# design.net
KiCad netlist of a schematic drawn in Altium Designer
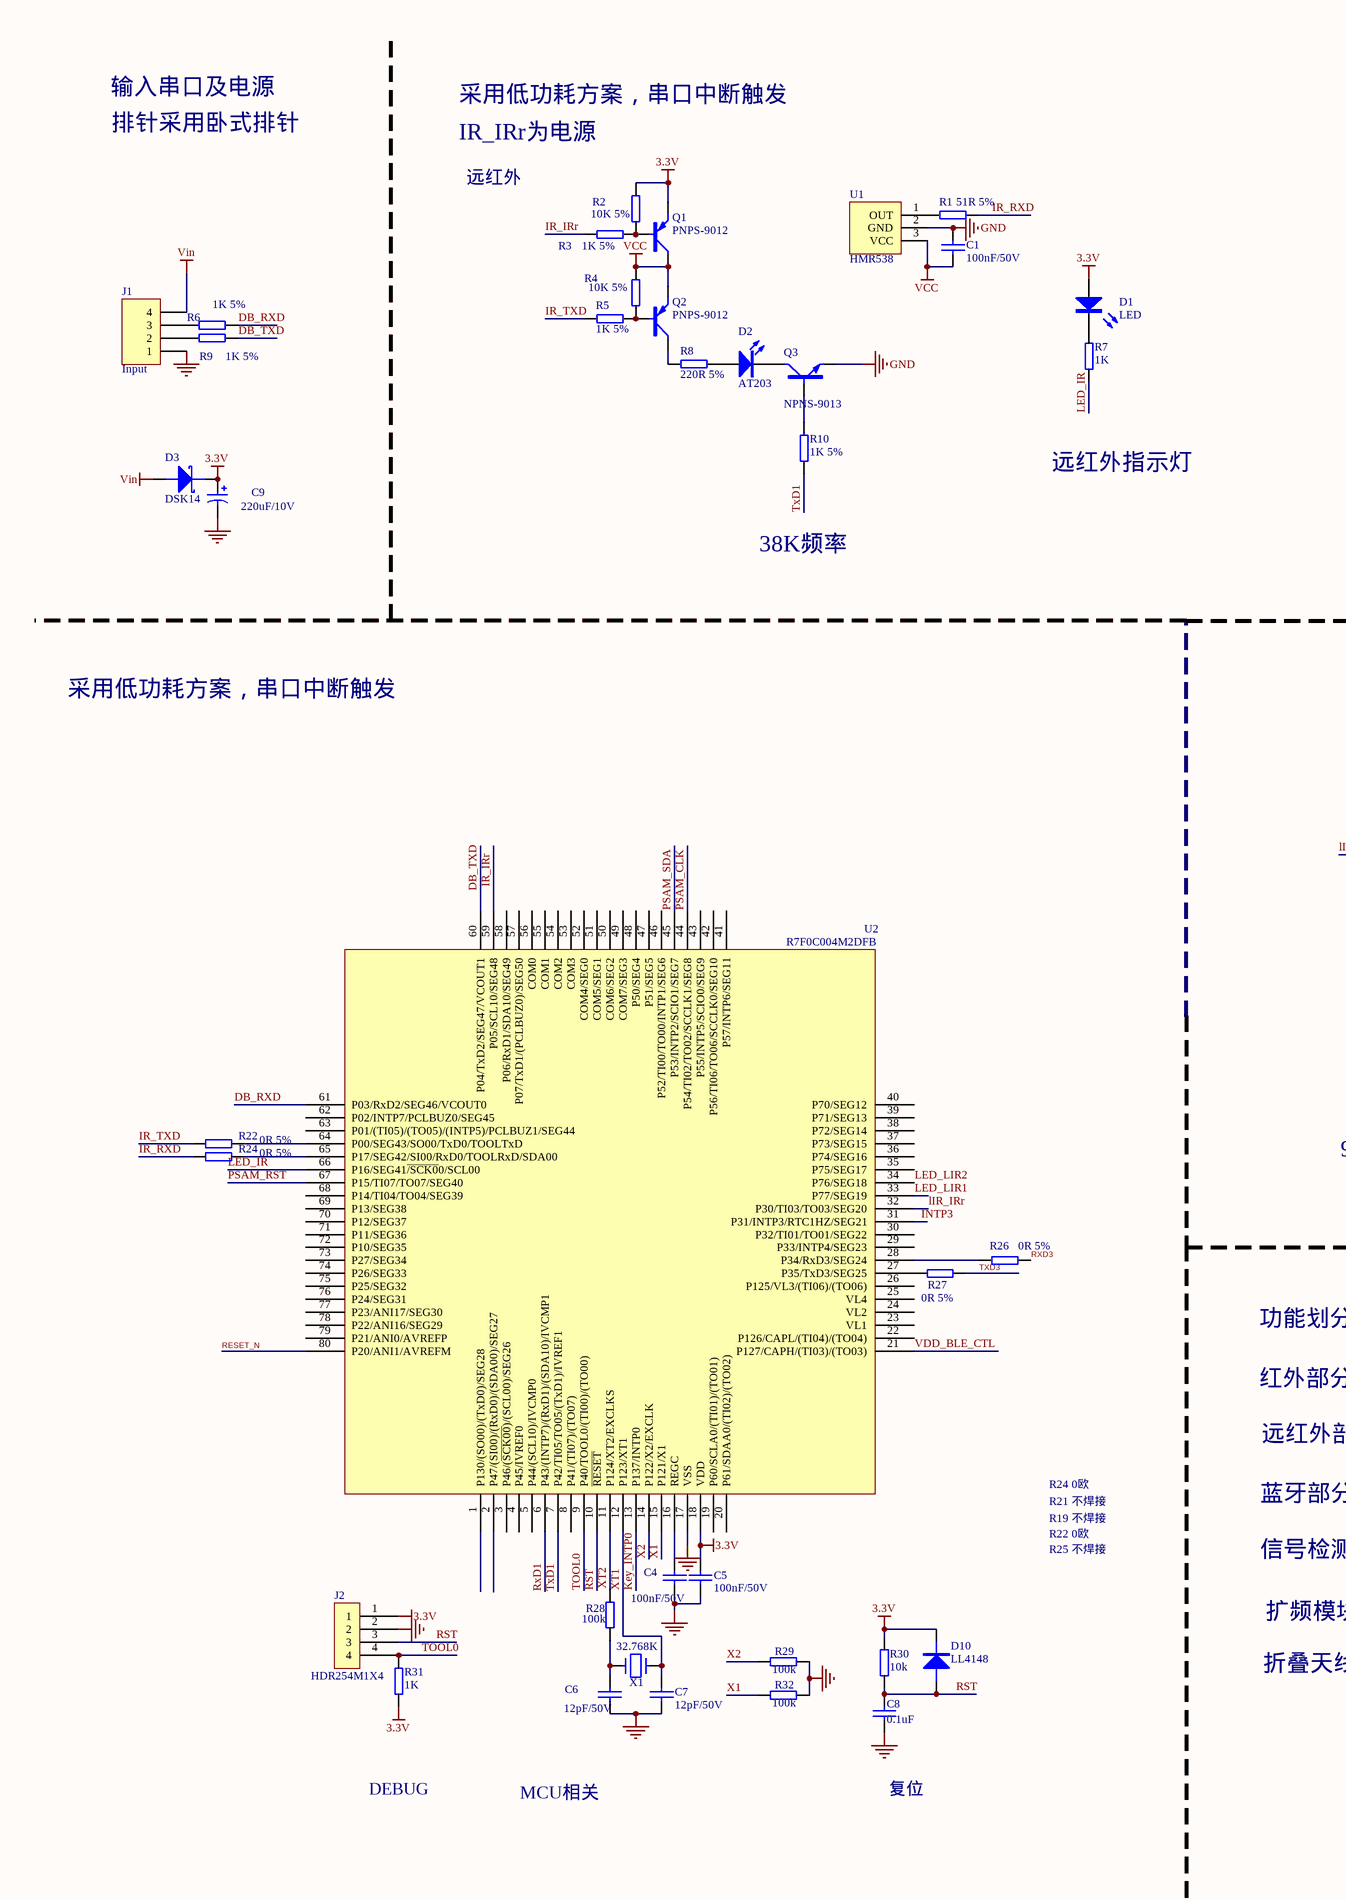
[diagram p0: 多合一红外工具.SchDoc, left]
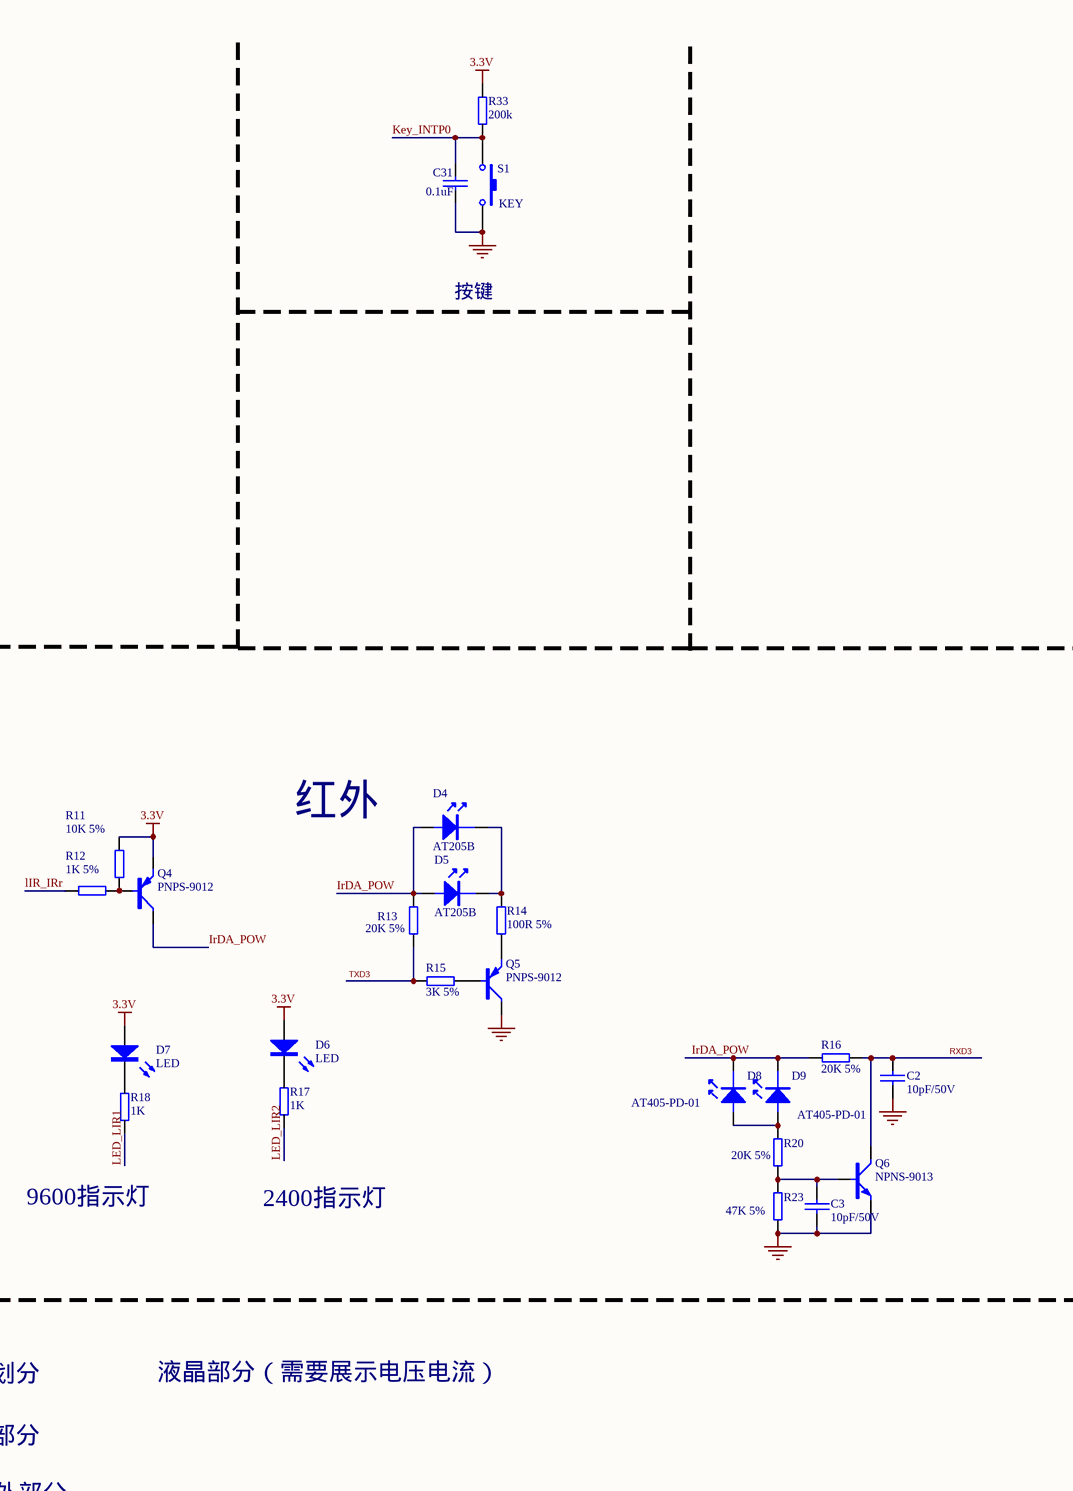
[diagram p1: 多合一红外工具.SchDoc, right]

(export (version "E")
  (design (tool "Eeschema 10.0.6"))
  (components
    (comp (ref "C1")
      (value "100nF/50V")
      (footprint "CAP0603")
      (description "104pF,50 V,±10%,0603,国巨,CC0603KRX7R9BB104")
      (fields (field (name "PART NUMBER") "101020103-0021"))
      (libsource (lib "Database_Libs2") (part "CC03K7R9_100N"))
    )
    (comp (ref "C2")
      (value "10pF/50V")
      (footprint "CAP0603")
      (description "10pF,50 V,±5%,0603,X7R,国巨,CC0603JRNPO9BN100")
      (fields (field (name "PART NUMBER") "101020103-0014"))
      (libsource (lib "Database_Libs2") (part "CC03JPO9_10P"))
    )
    (comp (ref "C3")
      (value "10pF/50V")
      (footprint "CAP0603")
      (description "10pF,50 V,±5%,0603,X7R,国巨,CC0603JRNPO9BN100")
      (fields (field (name "PART NUMBER") "101020103-0014"))
      (libsource (lib "Database_Libs2") (part "CC03JPO9_10P"))
    )
    (comp (ref "C4")
      (value "100nF/50V")
      (footprint "CAP0603")
      (description "104pF,50 V,±10%,0603,国巨,CC0603KRX7R9BB104")
      (fields (field (name "PART NUMBER") "101020103-0021"))
      (libsource (lib "Database_Libs2") (part "CC03K7R9_100N"))
    )
    (comp (ref "C5")
      (value "100nF/50V")
      (footprint "CAP0603")
      (description "104pF,50 V,±10%,0603,国巨,CC0603KRX7R9BB104")
      (fields (field (name "PART NUMBER") "101020103-0021"))
      (libsource (lib "Database_Libs2") (part "CC03K7R9_100N"))
    )
    (comp (ref "C6")
      (value "12pF/50V")
      (footprint "CAP0603")
      (description "12P,50 V,±5%,0603,国巨,CC0603JRNPO9BN12")
      (fields (field (name "PART NUMBER") "101020103-0005"))
      (libsource (lib "Database_Libs2") (part "CC03JPO9_12P"))
    )
    (comp (ref "C7")
      (value "12pF/50V")
      (footprint "CAP0603")
      (description "12P,50 V,±5%,0603,国巨,CC0603JRNPO9BN12")
      (fields (field (name "PART NUMBER") "101020103-0005"))
      (libsource (lib "Database_Libs2") (part "CC03JPO9_12P"))
    )
    (comp (ref "C8")
      (value "0.1uF")
      (footprint "C0603")
      (description "无极性电容")
      (libsource (lib "CBB_Lib_SCH") (part "CAP"))
    )
    (comp (ref "C9")
      (value "220uF/10V")
      (footprint "CAT7343")
      (description "220uF,10 V,±10%,7343,AVX/ KEMET,T491D227K010AT")
      (fields (field (name "PART NUMBER") "1010205-0001"))
      (libsource (lib "Database_Libs2") (part "CT6MATAJ_220U"))
    )
    (comp (ref "C31")
      (value "0.1uF")
      (footprint "C0603")
      (description "无极性电容")
      (libsource (lib "CBB_Lib_SCH") (part "CAP"))
    )
    (comp (ref "D1")
      (value "LED")
      (footprint "LED2_300")
      (description "圆形插件,3mm 圆形,插件,红光,湖北匡通电子有限公司,3BB4HC")
      (fields (field (name "PART NUMBER") "101040102-0001"))
      (libsource (lib "Database_Libs2") (part "01-LED_T3R"))
    )
    (comp (ref "D2")
      (value "AT203")
      (footprint "IR_254_532_300")
      (description "DIP-2,φ3,插件,红光,上海品观电子有限公司/可得,AT203")
      (fields (field (name "PART NUMBER") "101040102-0010"))
      (libsource (lib "Database_Libs2") (part "01_AT203"))
    )
    (comp (ref "D3")
      (value "DSK14")
      (footprint "SOD-123FL")
      (description "DSK14,SOD-123FL,1 A,40 V,28 V,台湾强茂集团苏州群鑫电子,DSK14")
      (fields (field (name "PART NUMBER") "101040101-0043"))
      (libsource (lib "Database_Libs2") (part "02_DSK14"))
    )
    (comp (ref "D4")
      (value "AT205B")
      (footprint "IR_254_1000_500")
      (description "直插,Φ5.8mm圆头透明色，,0.1 A,4 V,5 V,上海品观电子有限公司,AT205B")
      (fields (field (name "PART NUMBER") "101040101-0034"))
      (libsource (lib "Database_Libs2") (part "01_AT205B"))
    )
    (comp (ref "D5")
      (value "AT205B")
      (footprint "IR_254_1000_500")
      (description "直插,Φ5.8mm圆头透明色，,0.1 A,4 V,5 V,上海品观电子有限公司,AT205B")
      (fields (field (name "PART NUMBER") "101040101-0034"))
      (libsource (lib "Database_Libs2") (part "01_AT205B"))
    )
    (comp (ref "D6")
      (value "LED")
      (footprint "LED2_300")
      (description "圆形插件,3mm 圆形,插件,红光,湖北匡通电子有限公司,3BB4HC")
      (fields (field (name "PART NUMBER") "101040102-0001"))
      (libsource (lib "Database_Libs2") (part "01-LED_T3R"))
    )
    (comp (ref "D7")
      (value "LED")
      (footprint "LED2_300")
      (description "圆形插件,3mm 圆形,插件,红光,湖北匡通电子有限公司,3BB4HC")
      (fields (field (name "PART NUMBER") "101040102-0001"))
      (libsource (lib "Database_Libs2") (part "01-LED_T3R"))
    )
    (comp (ref "D8")
      (value "AT405-PD-01")
      (footprint "IR_254_1000_500")
      (description "Φ5.8mm圆头黑色，光电接收管,Φ5.8mm,0.01 A,1.2 V,60 V,上海品观电子,AT405-PD-01")
      (fields (field (name "PART NUMBER") "101040101-0035"))
      (libsource (lib "Database_Libs2") (part "01_AT405-PD-01"))
    )
    (comp (ref "D9")
      (value "AT405-PD-01")
      (footprint "IR_254_1000_500")
      (description "Φ5.8mm圆头黑色，光电接收管,Φ5.8mm,0.01 A,1.2 V,60 V,上海品观电子,AT405-PD-01")
      (fields (field (name "PART NUMBER") "101040101-0035"))
      (libsource (lib "Database_Libs2") (part "01_AT405-PD-01"))
    )
    (comp (ref "D10")
      (value "LL4148")
      (footprint "SOD-123FL")
      (description "4148,4148,0.2 A,1 V,100 V,先科,LL4148")
      (fields (field (name "PART NUMBER") "101040101-0005"))
      (libsource (lib "Database_Libs2") (part "02_LL4148"))
    )
    (comp (ref "J1")
      (value "Input")
      (footprint "HDR1X4")
      (description "Header, 4-Pin")
      (libsource (lib "CBB_Lib_SCH") (part "Header 4"))
    )
    (comp (ref "J2")
      (value "HDR254M1X4")
      (footprint "HDR1X4")
      (fields (field (name "PUBLISHER") "Altium Limited"))
      (libsource (lib "SCH_LIB_WX") (part "HDR254M1X4"))
    )
    (comp (ref "Q1")
      (value "PNPS-9012")
      (footprint "SOT-23")
      (description "9012,PNP,SOT-23,JCET;长电,S9012")
      (fields (field (name "PART NUMBER") "101040201-0001"))
      (libsource (lib "Database_Libs2") (part "03_PNPS-9012"))
    )
    (comp (ref "Q2")
      (value "PNPS-9012")
      (footprint "SOT-23")
      (description "9012,PNP,SOT-23,JCET;长电,S9012")
      (fields (field (name "PART NUMBER") "101040201-0001"))
      (libsource (lib "Database_Libs2") (part "03_PNPS-9012"))
    )
    (comp (ref "Q3")
      (value "NPNS-9013")
      (footprint "SOT-23")
      (description "9013,NPN,SOT-23,长电,S9013")
      (fields (field (name "PART NUMBER") "101040201-0002"))
      (libsource (lib "Database_Libs2") (part "03_NPNS-9013"))
    )
    (comp (ref "Q4")
      (value "PNPS-9012")
      (footprint "SOT-23")
      (description "9012,PNP,SOT-23,JCET;长电,S9012")
      (fields (field (name "PART NUMBER") "101040201-0001"))
      (libsource (lib "Database_Libs2") (part "03_PNPS-9012"))
    )
    (comp (ref "Q5")
      (value "PNPS-9012")
      (footprint "SOT-23")
      (description "9012,PNP,SOT-23,JCET;长电,S9012")
      (fields (field (name "PART NUMBER") "101040201-0001"))
      (libsource (lib "Database_Libs2") (part "03_PNPS-9012"))
    )
    (comp (ref "Q6")
      (value "NPNS-9013")
      (footprint "SOT-23")
      (description "9013,NPN,SOT-23,长电,S9013")
      (fields (field (name "PART NUMBER") "101040201-0002"))
      (libsource (lib "Database_Libs2") (part "03_NPNS-9013"))
    )
    (comp (ref "R1")
      (value "51R 5%")
      (footprint "RES0603")
      (description "国巨,±5%,0603,,155 ℃,-55 ℃,RC0603JR-0751RL,无铅,100 ppm/℃,1/10W,,51欧")
      (fields (field (name "PART NUMBER") "101010103-0037"))
      (libsource (lib "Database_Libs2") (part "RC03J_51R"))
    )
    (comp (ref "R2")
      (value "10K 5%")
      (footprint "RES0603")
      (description "国巨,±5%,0603,,155 ℃,-55 ℃,RC0603JR-0710KL,无铅,200 ppm/℃,1/10W,,10K")
      (fields (field (name "PART NUMBER") "101010103-0003"))
      (libsource (lib "Database_Libs2") (part "RC03J_10K"))
    )
    (comp (ref "R3")
      (value "1K 5%")
      (footprint "RES0603")
      (description "1K,±5%,1/10W,0603,国巨,RC0603JR-071KL")
      (fields (field (name "PART NUMBER") "101010103-0008"))
      (libsource (lib "Database_Libs2") (part "RC03J_1K"))
    )
    (comp (ref "R4")
      (value "10K 5%")
      (footprint "RES0603")
      (description "国巨,±5%,0603,,155 ℃,-55 ℃,RC0603JR-0710KL,无铅,200 ppm/℃,1/10W,,10K")
      (fields (field (name "PART NUMBER") "101010103-0003"))
      (libsource (lib "Database_Libs2") (part "RC03J_10K"))
    )
    (comp (ref "R5")
      (value "1K 5%")
      (footprint "RES0603")
      (description "1K,±5%,1/10W,0603,国巨,RC0603JR-071KL")
      (fields (field (name "PART NUMBER") "101010103-0008"))
      (libsource (lib "Database_Libs2") (part "RC03J_1K"))
    )
    (comp (ref "R6")
      (value "1K 5%")
      (footprint "RES0603")
      (description "1K,±5%,1/10W,0603,国巨,RC0603JR-071KL")
      (fields (field (name "PART NUMBER") "101010103-0008"))
      (libsource (lib "Database_Libs2") (part "RC03J_1K"))
    )
    (comp (ref "R7") (value "1K") (footprint "R0603") (libsource (lib "CBB_Lib_SCH") (part "RES")))
    (comp (ref "R8")
      (value "220R 5%")
      (footprint "RES0603")
      (description "220±5%,1/10W,0603,国巨,RC0603JR-07220RL")
      (fields (field (name "PART NUMBER") "101010103-0019"))
      (libsource (lib "Database_Libs2") (part "RC03J_220R"))
    )
    (comp (ref "R9")
      (value "1K 5%")
      (footprint "RES0603")
      (description "1K,±5%,1/10W,0603,国巨,RC0603JR-071KL")
      (fields (field (name "PART NUMBER") "101010103-0008"))
      (libsource (lib "Database_Libs2") (part "RC03J_1K"))
    )
    (comp (ref "R10")
      (value "1K 5%")
      (footprint "RES0603")
      (description "1K,±5%,1/10W,0603,国巨,RC0603JR-071KL")
      (fields (field (name "PART NUMBER") "101010103-0008"))
      (libsource (lib "Database_Libs2") (part "RC03J_1K"))
    )
    (comp (ref "R11")
      (value "10K 5%")
      (footprint "RES0603")
      (description "国巨,±5%,0603,,155 ℃,-55 ℃,RC0603JR-0710KL,无铅,200 ppm/℃,1/10W,,10K")
      (fields (field (name "PART NUMBER") "101010103-0003"))
      (libsource (lib "Database_Libs2") (part "RC03J_10K"))
    )
    (comp (ref "R12")
      (value "1K 5%")
      (footprint "RES0603")
      (description "1K,±5%,1/10W,0603,国巨,RC0603JR-071KL")
      (fields (field (name "PART NUMBER") "101010103-0008"))
      (libsource (lib "Database_Libs2") (part "RC03J_1K"))
    )
    (comp (ref "R13")
      (value "20K 5%")
      (footprint "RES0603")
      (description "国巨,±5%,0603,,155 ℃,-55 ℃,RC0603JR-0720KL,无铅,200 ppm/℃,1/10W,,20K")
      (fields (field (name "PART NUMBER") "101010103-0004"))
      (libsource (lib "Database_Libs2") (part "RC03J_20K"))
    )
    (comp (ref "R14")
      (value "100R 5%")
      (footprint "RES0603")
      (description "100R,±5%,1/10W,0603,国巨,RC0603JR-07100RL")
      (fields (field (name "PART NUMBER") "101010103-0022"))
      (libsource (lib "Database_Libs2") (part "RC03J_100R"))
    )
    (comp (ref "R15")
      (value "3K 5%")
      (footprint "RES0603")
      (description "国巨,±5%,0603,,155 ℃,-55 ℃,RC0603JR-073KL,无铅,100 ppm/℃,1/10W,,3K")
      (fields (field (name "PART NUMBER") "101010103-0006"))
      (libsource (lib "Database_Libs2") (part "RC03J_3K"))
    )
    (comp (ref "R16")
      (value "20K 5%")
      (footprint "RES0603")
      (description "国巨,±5%,0603,,155 ℃,-55 ℃,RC0603JR-0720KL,无铅,200 ppm/℃,1/10W,,20K")
      (fields (field (name "PART NUMBER") "101010103-0004"))
      (libsource (lib "Database_Libs2") (part "RC03J_20K"))
    )
    (comp (ref "R17") (value "1K") (footprint "R0603") (libsource (lib "CBB_Lib_SCH") (part "RES")))
    (comp (ref "R18") (value "1K") (footprint "R0603") (libsource (lib "CBB_Lib_SCH") (part "RES")))
    (comp (ref "R20")
      (value "20K 5%")
      (footprint "RES0603")
      (description "国巨,±5%,0603,,155 ℃,-55 ℃,RC0603JR-0720KL,无铅,200 ppm/℃,1/10W,,20K")
      (fields (field (name "PART NUMBER") "101010103-0004"))
      (libsource (lib "Database_Libs2") (part "RC03J_20K"))
    )
    (comp (ref "R22")
      (value "0R 5%")
      (footprint "RES0603")
      (description "国巨,±5%,0603,,155 ℃,-55 ℃,RC0603J2-070RL,无铅,200 ppm/℃,1/10W,,0R")
      (fields (field (name "PART NUMBER") "101010103-0001"))
      (libsource (lib "Database_Libs2") (part "RC03J_0R"))
    )
    (comp (ref "R23")
      (value "47K 5%")
      (footprint "RES0603")
      (description "47K,±5%,1/10W,0603,国巨,RC0603JR-0747KL")
      (fields (field (name "PART NUMBER") "101010103-0012"))
      (libsource (lib "Database_Libs2") (part "RC03J_47K"))
    )
    (comp (ref "R24")
      (value "0R 5%")
      (footprint "RES0603")
      (description "国巨,±5%,0603,,155 ℃,-55 ℃,RC0603J2-070RL,无铅,200 ppm/℃,1/10W,,0R")
      (fields (field (name "PART NUMBER") "101010103-0001"))
      (libsource (lib "Database_Libs2") (part "RC03J_0R"))
    )
    (comp (ref "R26")
      (value "0R 5%")
      (footprint "RES0603")
      (description "国巨,±5%,0603,,155 ℃,-55 ℃,RC0603J2-070RL,无铅,200 ppm/℃,1/10W,,0R")
      (fields (field (name "PART NUMBER") "101010103-0001"))
      (libsource (lib "Database_Libs2") (part "RC03J_0R"))
    )
    (comp (ref "R27")
      (value "0R 5%")
      (footprint "RES0603")
      (description "国巨,±5%,0603,,155 ℃,-55 ℃,RC0603J2-070RL,无铅,200 ppm/℃,1/10W,,0R")
      (fields (field (name "PART NUMBER") "101010103-0001"))
      (libsource (lib "Database_Libs2") (part "RC03J_0R"))
    )
    (comp (ref "R28") (value "100k") (footprint "R0603") (libsource (lib "CBB_Lib_SCH") (part "RES")))
    (comp (ref "R29") (value "100k") (footprint "R0603") (libsource (lib "CBB_Lib_SCH") (part "RES")))
    (comp (ref "R30") (value "10k") (footprint "R0603") (libsource (lib "CBB_Lib_SCH") (part "RES")))
    (comp (ref "R31") (value "1K") (footprint "R0603") (libsource (lib "CBB_Lib_SCH") (part "RES")))
    (comp (ref "R32") (value "100k") (footprint "R0603") (libsource (lib "CBB_Lib_SCH") (part "RES")))
    (comp (ref "R33") (value "200k") (footprint "R0603") (libsource (lib "CBB_Lib_SCH") (part "RES")))
    (comp (ref "S1")
      (value "KEY")
      (footprint "KEY-6*6")
      (description "Switch")
      (libsource (lib "CBB_Lib_SCH") (part "SW-PB"))
    )
    (comp (ref "U1") (value "HMR538") (footprint "HM538R1") (libsource (lib "IC_S") (part "HMR538")))
    (comp (ref "U2")
      (value "R7F0C004M2DFB")
      (footprint "LQFP80")
      (description "LQFP80,贴片,瑞萨,R7F0C004M2DFB")
      (fields (field (name "PART NUMBER") "1010502-0046"))
      (libsource (lib "Database_Libs2") (part "05_R7F0C004M2DFB"))
    )
    (comp (ref "X1")
      (value "32.768K")
      (footprint "XTAL-2S")
      (description "晶振,2PIN")
      (libsource (lib "CBB_Lib_SCH") (part "XTAL1"))
    )
  )
  (nets
    (net (code "1") (name "/DB_RXD") (class "Default")
      (node (ref "R6") (pin "2") (pinfunction "2_2") (pintype "passive"))
      (node (ref "U2") (pin "61") (pinfunction "P03/RxD2/SEG46/VCOUT0_61") (pintype "passive"))
    )
    (net (code "2") (name "/DB_TXD") (class "Default")
      (node (ref "R9") (pin "2") (pinfunction "2_2") (pintype "passive"))
      (node (ref "U2") (pin "60") (pinfunction "P04/TxD2/SEG47/VCOUT1_60") (pintype "passive"))
    )
    (net (code "3") (name "/INTP3") (class "Default")
      (node (ref "U2") (pin "31") (pinfunction "P31/INTP3/RTC1HZ/SEG21_31") (pintype "passive"))
    )
    (net (code "4") (name "/IR_IRr") (class "Default")
      (node (ref "R3") (pin "1") (pinfunction "1_1") (pintype "passive"))
      (node (ref "U2") (pin "59") (pinfunction "P05/SCL10/SEG48_59") (pintype "passive"))
    )
    (net (code "5") (name "/IR_RXD") (class "Default")
      (node (ref "R1") (pin "2") (pinfunction "2_2") (pintype "passive"))
      (node (ref "R24") (pin "1") (pinfunction "1_1") (pintype "passive"))
    )
    (net (code "6") (name "/IR_TXD") (class "Default")
      (node (ref "R22") (pin "1") (pinfunction "1_1") (pintype "passive"))
      (node (ref "R5") (pin "1") (pinfunction "1_1") (pintype "passive"))
    )
    (net (code "7") (name "/IrDA_POW") (class "Default")
      (node (ref "D4") (pin "1") (pinfunction "1_1") (pintype "passive"))
      (node (ref "D5") (pin "1") (pinfunction "1_1") (pintype "passive"))
      (node (ref "D8") (pin "2") (pinfunction "2_2") (pintype "passive"))
      (node (ref "D9") (pin "2") (pinfunction "2_2") (pintype "passive"))
      (node (ref "Q4") (pin "3") (pinfunction "C_3") (pintype "passive"))
      (node (ref "R13") (pin "2") (pinfunction "2_2") (pintype "passive"))
      (node (ref "R16") (pin "1") (pinfunction "1_1") (pintype "passive"))
    )
    (net (code "8") (name "/Key_INTP0") (class "Default")
      (node (ref "C31") (pin "2") (pintype "passive"))
      (node (ref "R33") (pin "1") (pintype "passive"))
      (node (ref "S1") (pin "1") (pinfunction "1_1") (pintype "passive"))
      (node (ref "U2") (pin "13") (pinfunction "P137/INTP0_13") (pintype "passive"))
    )
    (net (code "9") (name "/LED_IR") (class "Default")
      (node (ref "R7") (pin "1") (pintype "passive"))
      (node (ref "U2") (pin "66") (pinfunction "P16/SEG41~{/SCK0}0/SCL00_66") (pintype "passive"))
    )
    (net (code "10") (name "/LED_LIR1") (class "Default")
      (node (ref "R18") (pin "1") (pintype "passive"))
      (node (ref "U2") (pin "33") (pinfunction "P77/SEG19_33") (pintype "passive"))
    )
    (net (code "11") (name "/LED_LIR2") (class "Default")
      (node (ref "R17") (pin "1") (pintype "passive"))
      (node (ref "U2") (pin "34") (pinfunction "P76/SEG18_34") (pintype "passive"))
    )
    (net (code "12") (name "/PSAM_CLK") (class "Default")
      (node (ref "U2") (pin "44") (pinfunction "P54/TI02/TO02/SCCLK1/SEG8_44") (pintype "passive"))
    )
    (net (code "13") (name "/PSAM_RST") (class "Default")
      (node (ref "U2") (pin "67") (pinfunction "P15/TI07/TO07/SEG40_67") (pintype "passive"))
    )
    (net (code "14") (name "/PSAM_SDA") (class "Default")
      (node (ref "U2") (pin "45") (pinfunction "P53/INTP2/SCIO1/SEG7_45") (pintype "passive"))
    )
    (net (code "15") (name "/RESET_N") (class "Default")
      (node (ref "U2") (pin "80") (pinfunction "P20/ANI1/AVREFM_80") (pintype "passive"))
    )
    (net (code "16") (name "/RST") (class "Default")
      (node (ref "C8") (pin "2") (pintype "passive"))
      (node (ref "D10") (pin "1") (pinfunction "1_1") (pintype "passive"))
      (node (ref "J2") (pin "3") (pinfunction "3_3") (pintype "passive"))
      (node (ref "R30") (pin "1") (pintype "passive"))
      (node (ref "U2") (pin "10") (pinfunction "~{RESET}_10") (pintype "passive"))
    )
    (net (code "17") (name "/RXD3") (class "Default")
      (node (ref "C2") (pin "1") (pinfunction "1_1") (pintype "passive"))
      (node (ref "Q6") (pin "3") (pinfunction "C_3") (pintype "passive"))
      (node (ref "R16") (pin "2") (pinfunction "2_2") (pintype "passive"))
      (node (ref "R26") (pin "2") (pinfunction "2_2") (pintype "passive"))
    )
    (net (code "18") (name "/RxD1") (class "Default")
      (node (ref "U2") (pin "6") (pinfunction "P43/(INTP7)/(RxD1)/(SDA10)/IVCMP1_6") (pintype "passive"))
    )
    (net (code "19") (name "/TOOL0") (class "Default")
      (node (ref "J2") (pin "4") (pinfunction "4_4") (pintype "passive"))
      (node (ref "R31") (pin "2") (pintype "passive"))
      (node (ref "U2") (pin "9") (pinfunction "P40/TOOL0/(TI00)/(TO00)_9") (pintype "passive"))
    )
    (net (code "20") (name "/TXD3") (class "Default")
      (node (ref "R13") (pin "1") (pinfunction "1_1") (pintype "passive"))
      (node (ref "R15") (pin "1") (pinfunction "1_1") (pintype "passive"))
      (node (ref "R27") (pin "2") (pinfunction "2_2") (pintype "passive"))
    )
    (net (code "21") (name "/TxD1") (class "Default")
      (node (ref "R10") (pin "2") (pinfunction "2_2") (pintype "passive"))
      (node (ref "U2") (pin "7") (pinfunction "P42/TI05/TO05/(TxD1)/IVREF1_7") (pintype "passive"))
    )
    (net (code "22") (name "/VDD_BLE_CTL") (class "Default")
      (node (ref "U2") (pin "21") (pinfunction "P127/CAPH/(TI03)/(TO03)_21") (pintype "passive"))
    )
    (net (code "23") (name "/X1") (class "Default")
      (node (ref "R32") (pin "2") (pintype "passive"))
      (node (ref "U2") (pin "15") (pinfunction "P121/X1_15") (pintype "passive"))
    )
    (net (code "24") (name "/X2") (class "Default")
      (node (ref "R29") (pin "2") (pintype "passive"))
      (node (ref "U2") (pin "14") (pinfunction "P122/X2/EXCLK_14") (pintype "passive"))
    )
    (net (code "25") (name "/XT1") (class "Default")
      (node (ref "C7") (pin "1") (pinfunction "1_1") (pintype "passive"))
      (node (ref "U2") (pin "12") (pinfunction "P123/XT1_12") (pintype "passive"))
      (node (ref "X1") (pin "1") (pinfunction "1_1") (pintype "passive"))
    )
    (net (code "26") (name "/XT2") (class "Default")
      (node (ref "R28") (pin "2") (pintype "passive"))
      (node (ref "U2") (pin "11") (pinfunction "P124/XT2/EXCLKS_11") (pintype "passive"))
    )
    (net (code "27") (name "/lIR_IRr") (class "Default")
      (node (ref "R12") (pin "1") (pinfunction "1_1") (pintype "passive"))
      (node (ref "U2") (pin "32") (pinfunction "P30/TI03/TO03/SEG20_32") (pintype "passive"))
    )
    (net (code "28") (name "3.3V") (class "Default")
      (node (ref "C5") (pin "2") (pinfunction "2_2") (pintype "passive"))
      (node (ref "C9") (pin "1") (pinfunction "1_1") (pintype "passive"))
      (node (ref "D1") (pin "1") (pinfunction "1_1") (pintype "passive"))
      (node (ref "D10") (pin "2") (pinfunction "2_2") (pintype "passive"))
      (node (ref "D3") (pin "2") (pinfunction "2_2") (pintype "passive"))
      (node (ref "D6") (pin "1") (pinfunction "1_1") (pintype "passive"))
      (node (ref "D7") (pin "1") (pinfunction "1_1") (pintype "passive"))
      (node (ref "J2") (pin "1") (pinfunction "1_1") (pintype "passive"))
      (node (ref "Q1") (pin "2") (pinfunction "E_2") (pintype "passive"))
      (node (ref "Q4") (pin "2") (pinfunction "E_2") (pintype "passive"))
      (node (ref "R11") (pin "2") (pinfunction "2_2") (pintype "passive"))
      (node (ref "R2") (pin "2") (pinfunction "2_2") (pintype "passive"))
      (node (ref "R30") (pin "2") (pintype "passive"))
      (node (ref "R31") (pin "1") (pintype "passive"))
      (node (ref "R33") (pin "2") (pintype "passive"))
      (node (ref "U2") (pin "18") (pinfunction "VDD_18") (pintype "passive"))
    )
    (net (code "29") (name "GND") (class "Default")
      (node (ref "C1") (pin "1") (pinfunction "1_1") (pintype "passive"))
      (node (ref "C2") (pin "2") (pinfunction "2_2") (pintype "passive"))
      (node (ref "C3") (pin "2") (pinfunction "2_2") (pintype "passive"))
      (node (ref "C31") (pin "1") (pintype "passive"))
      (node (ref "C4") (pin "2") (pinfunction "2_2") (pintype "passive"))
      (node (ref "C5") (pin "1") (pinfunction "1_1") (pintype "passive"))
      (node (ref "C6") (pin "2") (pinfunction "2_2") (pintype "passive"))
      (node (ref "C7") (pin "2") (pinfunction "2_2") (pintype "passive"))
      (node (ref "C8") (pin "1") (pintype "passive"))
      (node (ref "C9") (pin "2") (pinfunction "2_2") (pintype "passive"))
      (node (ref "J1") (pin "1") (pinfunction "1_1") (pintype "passive"))
      (node (ref "J2") (pin "2") (pinfunction "2_2") (pintype "passive"))
      (node (ref "Q3") (pin "2") (pinfunction "E_2") (pintype "passive"))
      (node (ref "Q5") (pin "3") (pinfunction "C_3") (pintype "passive"))
      (node (ref "Q6") (pin "2") (pinfunction "E_2") (pintype "passive"))
      (node (ref "R23") (pin "1") (pinfunction "1_1") (pintype "passive"))
      (node (ref "R29") (pin "1") (pintype "passive"))
      (node (ref "R32") (pin "1") (pintype "passive"))
      (node (ref "S1") (pin "2") (pinfunction "2_2") (pintype "passive"))
      (node (ref "U1") (pin "2") (pinfunction "GND_2") (pintype "passive"))
      (node (ref "U2") (pin "17") (pinfunction "VSS_17") (pintype "passive"))
    )
    (net (code "30") (name "Net-(C6-Pad1)") (class "Default")
      (node (ref "C6") (pin "1") (pinfunction "1_1") (pintype "passive"))
      (node (ref "R28") (pin "1") (pintype "passive"))
      (node (ref "X1") (pin "2") (pinfunction "2_2") (pintype "passive"))
    )
    (net (code "31") (name "Net-(D1-Pad2)") (class "Default")
      (node (ref "D1") (pin "2") (pinfunction "2_2") (pintype "passive"))
      (node (ref "R7") (pin "2") (pintype "passive"))
    )
    (net (code "32") (name "Net-(D2-A)") (class "Default")
      (node (ref "D2") (pin "1") (pinfunction "A_1") (pintype "passive"))
      (node (ref "R8") (pin "2") (pinfunction "2_2") (pintype "passive"))
    )
    (net (code "33") (name "Net-(D2-K)") (class "Default")
      (node (ref "D2") (pin "2") (pinfunction "K_2") (pintype "passive"))
      (node (ref "Q3") (pin "3") (pinfunction "C_3") (pintype "passive"))
    )
    (net (code "34") (name "Net-(D4-Pad2)") (class "Default")
      (node (ref "D4") (pin "2") (pinfunction "2_2") (pintype "passive"))
      (node (ref "D5") (pin "2") (pinfunction "2_2") (pintype "passive"))
      (node (ref "R14") (pin "2") (pinfunction "2_2") (pintype "passive"))
    )
    (net (code "35") (name "Net-(D6-Pad2)") (class "Default")
      (node (ref "D6") (pin "2") (pinfunction "2_2") (pintype "passive"))
      (node (ref "R17") (pin "2") (pintype "passive"))
    )
    (net (code "36") (name "Net-(D7-Pad2)") (class "Default")
      (node (ref "D7") (pin "2") (pinfunction "2_2") (pintype "passive"))
      (node (ref "R18") (pin "2") (pintype "passive"))
    )
    (net (code "37") (name "Net-(D8-Pad1)") (class "Default")
      (node (ref "D8") (pin "1") (pinfunction "1_1") (pintype "passive"))
      (node (ref "D9") (pin "1") (pinfunction "1_1") (pintype "passive"))
      (node (ref "R20") (pin "2") (pinfunction "2_2") (pintype "passive"))
    )
    (net (code "38") (name "Net-(J1-Pad2)") (class "Default")
      (node (ref "J1") (pin "2") (pinfunction "2_2") (pintype "passive"))
      (node (ref "R9") (pin "1") (pinfunction "1_1") (pintype "passive"))
    )
    (net (code "39") (name "Net-(J1-Pad3)") (class "Default")
      (node (ref "J1") (pin "3") (pinfunction "3_3") (pintype "passive"))
      (node (ref "R6") (pin "1") (pinfunction "1_1") (pintype "passive"))
    )
    (net (code "40") (name "Net-(Q1-B)") (class "Default")
      (node (ref "Q1") (pin "1") (pinfunction "B_1") (pintype "passive"))
      (node (ref "R2") (pin "1") (pinfunction "1_1") (pintype "passive"))
      (node (ref "R3") (pin "2") (pinfunction "2_2") (pintype "passive"))
    )
    (net (code "41") (name "Net-(Q2-B)") (class "Default")
      (node (ref "Q2") (pin "1") (pinfunction "B_1") (pintype "passive"))
      (node (ref "R4") (pin "1") (pinfunction "1_1") (pintype "passive"))
      (node (ref "R5") (pin "2") (pinfunction "2_2") (pintype "passive"))
    )
    (net (code "42") (name "Net-(Q2-C)") (class "Default")
      (node (ref "Q2") (pin "3") (pinfunction "C_3") (pintype "passive"))
      (node (ref "R8") (pin "1") (pinfunction "1_1") (pintype "passive"))
    )
    (net (code "43") (name "Net-(Q3-B)") (class "Default")
      (node (ref "Q3") (pin "1") (pinfunction "B_1") (pintype "passive"))
      (node (ref "R10") (pin "1") (pinfunction "1_1") (pintype "passive"))
    )
    (net (code "44") (name "Net-(Q4-B)") (class "Default")
      (node (ref "Q4") (pin "1") (pinfunction "B_1") (pintype "passive"))
      (node (ref "R11") (pin "1") (pinfunction "1_1") (pintype "passive"))
      (node (ref "R12") (pin "2") (pinfunction "2_2") (pintype "passive"))
    )
    (net (code "45") (name "Net-(Q5-B)") (class "Default")
      (node (ref "Q5") (pin "1") (pinfunction "B_1") (pintype "passive"))
      (node (ref "R15") (pin "2") (pinfunction "2_2") (pintype "passive"))
    )
    (net (code "46") (name "Net-(Q5-E)") (class "Default")
      (node (ref "Q5") (pin "2") (pinfunction "E_2") (pintype "passive"))
      (node (ref "R14") (pin "1") (pinfunction "1_1") (pintype "passive"))
    )
    (net (code "47") (name "Net-(Q6-B)") (class "Default")
      (node (ref "C3") (pin "1") (pinfunction "1_1") (pintype "passive"))
      (node (ref "Q6") (pin "1") (pinfunction "B_1") (pintype "passive"))
      (node (ref "R20") (pin "1") (pinfunction "1_1") (pintype "passive"))
      (node (ref "R23") (pin "2") (pinfunction "2_2") (pintype "passive"))
    )
    (net (code "48") (name "Net-(U1-OUT)") (class "Default")
      (node (ref "R1") (pin "1") (pinfunction "1_1") (pintype "passive"))
      (node (ref "U1") (pin "1") (pinfunction "OUT_1") (pintype "passive"))
    )
    (net (code "49") (name "Net-(U2-P00{slash}SEG43{slash}SO00{slash}TxD0{slash}TOOLTxD)") (class "Default")
      (node (ref "R22") (pin "2") (pinfunction "2_2") (pintype "passive"))
      (node (ref "U2") (pin "64") (pinfunction "P00/SEG43/SO00/TxD0/TOOLTxD_64") (pintype "passive"))
    )
    (net (code "50") (name "Net-(U2-P17{slash}SEG42{slash}SI00{slash}RxD0{slash}TOOLRxD{slash}SDA00)") (class "Default")
      (node (ref "R24") (pin "2") (pinfunction "2_2") (pintype "passive"))
      (node (ref "U2") (pin "65") (pinfunction "P17/SEG42/SI00/RxD0/TOOLRxD/SDA00_65") (pintype "passive"))
    )
    (net (code "51") (name "Net-(U2-P34{slash}RxD3{slash}SEG24)") (class "Default")
      (node (ref "R26") (pin "1") (pinfunction "1_1") (pintype "passive"))
      (node (ref "U2") (pin "28") (pinfunction "P34/RxD3/SEG24_28") (pintype "passive"))
    )
    (net (code "52") (name "Net-(U2-P35{slash}TxD3{slash}SEG25)") (class "Default")
      (node (ref "R27") (pin "1") (pinfunction "1_1") (pintype "passive"))
      (node (ref "U2") (pin "27") (pinfunction "P35/TxD3/SEG25_27") (pintype "passive"))
    )
    (net (code "53") (name "Net-(U2-REGC)") (class "Default")
      (node (ref "C4") (pin "1") (pinfunction "1_1") (pintype "passive"))
      (node (ref "U2") (pin "16") (pinfunction "REGC_16") (pintype "passive"))
    )
    (net (code "54") (name "VCC") (class "Default")
      (node (ref "C1") (pin "2") (pinfunction "2_2") (pintype "passive"))
      (node (ref "Q1") (pin "3") (pinfunction "C_3") (pintype "passive"))
      (node (ref "Q2") (pin "2") (pinfunction "E_2") (pintype "passive"))
      (node (ref "R4") (pin "2") (pinfunction "2_2") (pintype "passive"))
      (node (ref "U1") (pin "3") (pinfunction "VCC_3") (pintype "passive"))
    )
    (net (code "55") (name "Vin") (class "Default")
      (node (ref "D3") (pin "1") (pinfunction "1_1") (pintype "passive"))
      (node (ref "J1") (pin "4") (pinfunction "4_4") (pintype "passive"))
    )
    (net (code "56") (name "unconnected-(U2-COM0-Pad56)") (class "Default")
      (node (ref "U2") (pin "56") (pinfunction "COM0_56") (pintype "passive"))
    )
    (net (code "57") (name "unconnected-(U2-COM1-Pad55)") (class "Default")
      (node (ref "U2") (pin "55") (pinfunction "COM1_55") (pintype "passive"))
    )
    (net (code "58") (name "unconnected-(U2-COM2-Pad54)") (class "Default")
      (node (ref "U2") (pin "54") (pinfunction "COM2_54") (pintype "passive"))
    )
    (net (code "59") (name "unconnected-(U2-COM3-Pad53)") (class "Default")
      (node (ref "U2") (pin "53") (pinfunction "COM3_53") (pintype "passive"))
    )
    (net (code "60") (name "unconnected-(U2-COM4{slash}SEG0-Pad52)") (class "Default")
      (node (ref "U2") (pin "52") (pinfunction "COM4/SEG0_52") (pintype "passive"))
    )
    (net (code "61") (name "unconnected-(U2-COM5{slash}SEG1-Pad51)") (class "Default")
      (node (ref "U2") (pin "51") (pinfunction "COM5/SEG1_51") (pintype "passive"))
    )
    (net (code "62") (name "unconnected-(U2-COM6{slash}SEG2-Pad50)") (class "Default")
      (node (ref "U2") (pin "50") (pinfunction "COM6/SEG2_50") (pintype "passive"))
    )
    (net (code "63") (name "unconnected-(U2-COM7{slash}SEG3-Pad49)") (class "Default")
      (node (ref "U2") (pin "49") (pinfunction "COM7/SEG3_49") (pintype "passive"))
    )
    (net (code "64") (name "unconnected-(U2-P01{slash}(TI05){slash}(TO05){slash}(INTP5){slash}PCLBUZ1{slash}SEG44-Pad63)") (class "Default")
      (node (ref "U2") (pin "63") (pinfunction "P01/(TI05)/(TO05)/(INTP5)/PCLBUZ1/SEG44_63") (pintype "passive"))
    )
    (net (code "65") (name "unconnected-(U2-P02{slash}INTP7{slash}PCLBUZ0{slash}SEG45-Pad62)") (class "Default")
      (node (ref "U2") (pin "62") (pinfunction "P02/INTP7/PCLBUZ0/SEG45_62") (pintype "passive"))
    )
    (net (code "66") (name "unconnected-(U2-P06{slash}RxD1{slash}SDA10{slash}SEG49-Pad58)") (class "Default")
      (node (ref "U2") (pin "58") (pinfunction "P06/RxD1/SDA10/SEG49_58") (pintype "passive"))
    )
    (net (code "67") (name "unconnected-(U2-P07{slash}TxD1{slash}(PCLBUZ0){slash}SEG50-Pad57)") (class "Default")
      (node (ref "U2") (pin "57") (pinfunction "P07/TxD1/(PCLBUZ0)/SEG50_57") (pintype "passive"))
    )
    (net (code "68") (name "unconnected-(U2-P10{slash}SEG35-Pad72)") (class "Default")
      (node (ref "U2") (pin "72") (pinfunction "P10/SEG35_72") (pintype "passive"))
    )
    (net (code "69") (name "unconnected-(U2-P11{slash}SEG36-Pad71)") (class "Default")
      (node (ref "U2") (pin "71") (pinfunction "P11/SEG36_71") (pintype "passive"))
    )
    (net (code "70") (name "unconnected-(U2-P12{slash}SEG37-Pad70)") (class "Default")
      (node (ref "U2") (pin "70") (pinfunction "P12/SEG37_70") (pintype "passive"))
    )
    (net (code "71") (name "unconnected-(U2-P13{slash}SEG38-Pad69)") (class "Default")
      (node (ref "U2") (pin "69") (pinfunction "P13/SEG38_69") (pintype "passive"))
    )
    (net (code "72") (name "unconnected-(U2-P14{slash}TI04{slash}TO04{slash}SEG39-Pad68)") (class "Default")
      (node (ref "U2") (pin "68") (pinfunction "P14/TI04/TO04/SEG39_68") (pintype "passive"))
    )
    (net (code "73") (name "unconnected-(U2-P21{slash}ANI0{slash}AVREFP-Pad79)") (class "Default")
      (node (ref "U2") (pin "79") (pinfunction "P21/ANI0/AVREFP_79") (pintype "passive"))
    )
    (net (code "74") (name "unconnected-(U2-P22{slash}ANI16{slash}SEG29-Pad78)") (class "Default")
      (node (ref "U2") (pin "78") (pinfunction "P22/ANI16/SEG29_78") (pintype "passive"))
    )
    (net (code "75") (name "unconnected-(U2-P23{slash}ANI17{slash}SEG30-Pad77)") (class "Default")
      (node (ref "U2") (pin "77") (pinfunction "P23/ANI17/SEG30_77") (pintype "passive"))
    )
    (net (code "76") (name "unconnected-(U2-P24{slash}SEG31-Pad76)") (class "Default")
      (node (ref "U2") (pin "76") (pinfunction "P24/SEG31_76") (pintype "passive"))
    )
    (net (code "77") (name "unconnected-(U2-P25{slash}SEG32-Pad75)") (class "Default")
      (node (ref "U2") (pin "75") (pinfunction "P25/SEG32_75") (pintype "passive"))
    )
    (net (code "78") (name "unconnected-(U2-P26{slash}SEG33-Pad74)") (class "Default")
      (node (ref "U2") (pin "74") (pinfunction "P26/SEG33_74") (pintype "passive"))
    )
    (net (code "79") (name "unconnected-(U2-P27{slash}SEG34-Pad73)") (class "Default")
      (node (ref "U2") (pin "73") (pinfunction "P27/SEG34_73") (pintype "passive"))
    )
    (net (code "80") (name "unconnected-(U2-P32{slash}TI01{slash}TO01{slash}SEG22-Pad30)") (class "Default")
      (node (ref "U2") (pin "30") (pinfunction "P32/TI01/TO01/SEG22_30") (pintype "passive"))
    )
    (net (code "81") (name "unconnected-(U2-P33{slash}INTP4{slash}SEG23-Pad29)") (class "Default")
      (node (ref "U2") (pin "29") (pinfunction "P33/INTP4/SEG23_29") (pintype "passive"))
    )
    (net (code "82") (name "unconnected-(U2-P41{slash}(TI07){slash}(TO07)-Pad8)") (class "Default")
      (node (ref "U2") (pin "8") (pinfunction "P41/(TI07)/(TO07)_8") (pintype "passive"))
    )
    (net (code "83") (name "unconnected-(U2-P44{slash}(SCL10){slash}IVCMP0-Pad5)") (class "Default")
      (node (ref "U2") (pin "5") (pinfunction "P44/(SCL10)/IVCMP0_5") (pintype "passive"))
    )
    (net (code "84") (name "unconnected-(U2-P45{slash}IVREF0-Pad4)") (class "Default")
      (node (ref "U2") (pin "4") (pinfunction "P45/IVREF0_4") (pintype "passive"))
    )
    (net (code "85") (name "unconnected-(U2-P46{slash}(~{SCK00}){slash}(SCL00){slash}SEG26-Pad3)") (class "Default")
      (node (ref "U2") (pin "3") (pinfunction "P46/(~{SCK00})/(SCL00)/SEG26_3") (pintype "passive"))
    )
    (net (code "86") (name "unconnected-(U2-P47{slash}(SI00){slash}(RxD0){slash}(SDA00){slash}SEG27-Pad2)") (class "Default")
      (node (ref "U2") (pin "2") (pinfunction "P47/(SI00)/(RxD0)/(SDA00)/SEG27_2") (pintype "passive"))
    )
    (net (code "87") (name "unconnected-(U2-P50{slash}SEG4-Pad48)") (class "Default")
      (node (ref "U2") (pin "48") (pinfunction "P50/SEG4_48") (pintype "passive"))
    )
    (net (code "88") (name "unconnected-(U2-P51{slash}SEG5-Pad47)") (class "Default")
      (node (ref "U2") (pin "47") (pinfunction "P51/SEG5_47") (pintype "passive"))
    )
    (net (code "89") (name "unconnected-(U2-P52{slash}TI00{slash}TO00{slash}INTP1{slash}SEG6-Pad46)") (class "Default")
      (node (ref "U2") (pin "46") (pinfunction "P52/TI00/TO00/INTP1/SEG6_46") (pintype "passive"))
    )
    (net (code "90") (name "unconnected-(U2-P55{slash}INTP5{slash}SCIO0{slash}SEG9-Pad43)") (class "Default")
      (node (ref "U2") (pin "43") (pinfunction "P55/INTP5/SCIO0/SEG9_43") (pintype "passive"))
    )
    (net (code "91") (name "unconnected-(U2-P56{slash}TI06{slash}TO06{slash}SCCLK0{slash}SEG10-Pad42)") (class "Default")
      (node (ref "U2") (pin "42") (pinfunction "P56/TI06/TO06/SCCLK0/SEG10_42") (pintype "passive"))
    )
    (net (code "92") (name "unconnected-(U2-P57{slash}INTP6{slash}SEG11-Pad41)") (class "Default")
      (node (ref "U2") (pin "41") (pinfunction "P57/INTP6/SEG11_41") (pintype "passive"))
    )
    (net (code "93") (name "unconnected-(U2-P60{slash}SCLA0{slash}(TI01){slash}(TO01)-Pad19)") (class "Default")
      (node (ref "U2") (pin "19") (pinfunction "P60/SCLA0/(TI01)/(TO01)_19") (pintype "passive"))
    )
    (net (code "94") (name "unconnected-(U2-P61{slash}SDAA0{slash}(TI02){slash}(TO02)-Pad20)") (class "Default")
      (node (ref "U2") (pin "20") (pinfunction "P61/SDAA0/(TI02)/(TO02)_20") (pintype "passive"))
    )
    (net (code "95") (name "unconnected-(U2-P70{slash}SEG12-Pad40)") (class "Default")
      (node (ref "U2") (pin "40") (pinfunction "P70/SEG12_40") (pintype "passive"))
    )
    (net (code "96") (name "unconnected-(U2-P71{slash}SEG13-Pad39)") (class "Default")
      (node (ref "U2") (pin "39") (pinfunction "P71/SEG13_39") (pintype "passive"))
    )
    (net (code "97") (name "unconnected-(U2-P72{slash}SEG14-Pad38)") (class "Default")
      (node (ref "U2") (pin "38") (pinfunction "P72/SEG14_38") (pintype "passive"))
    )
    (net (code "98") (name "unconnected-(U2-P73{slash}SEG15-Pad37)") (class "Default")
      (node (ref "U2") (pin "37") (pinfunction "P73/SEG15_37") (pintype "passive"))
    )
    (net (code "99") (name "unconnected-(U2-P74{slash}SEG16-Pad36)") (class "Default")
      (node (ref "U2") (pin "36") (pinfunction "P74/SEG16_36") (pintype "passive"))
    )
    (net (code "100") (name "unconnected-(U2-P75{slash}SEG17-Pad35)") (class "Default")
      (node (ref "U2") (pin "35") (pinfunction "P75/SEG17_35") (pintype "passive"))
    )
    (net (code "101") (name "unconnected-(U2-P125{slash}VL3{slash}(TI06){slash}(TO06)-Pad26)") (class "Default")
      (node (ref "U2") (pin "26") (pinfunction "P125/VL3/(TI06)/(TO06)_26") (pintype "passive"))
    )
    (net (code "102") (name "unconnected-(U2-P126{slash}CAPL{slash}(TI04){slash}(TO04)-Pad22)") (class "Default")
      (node (ref "U2") (pin "22") (pinfunction "P126/CAPL/(TI04)/(TO04)_22") (pintype "passive"))
    )
    (net (code "103") (name "unconnected-(U2-P130{slash}(SO00){slash}(TxD0){slash}SEG28-Pad1)") (class "Default")
      (node (ref "U2") (pin "1") (pinfunction "P130/(SO00)/(TxD0)/SEG28_1") (pintype "passive"))
    )
    (net (code "104") (name "unconnected-(U2-VL1-Pad23)") (class "Default")
      (node (ref "U2") (pin "23") (pinfunction "VL1_23") (pintype "passive"))
    )
    (net (code "105") (name "unconnected-(U2-VL2-Pad24)") (class "Default")
      (node (ref "U2") (pin "24") (pinfunction "VL2_24") (pintype "passive"))
    )
    (net (code "106") (name "unconnected-(U2-VL4-Pad25)") (class "Default")
      (node (ref "U2") (pin "25") (pinfunction "VL4_25") (pintype "passive"))
    )
  )
)
